# LPCB221_-_G210X_INTERFACE.net
KiCad netlist of a schematic drawn in Altium Designer
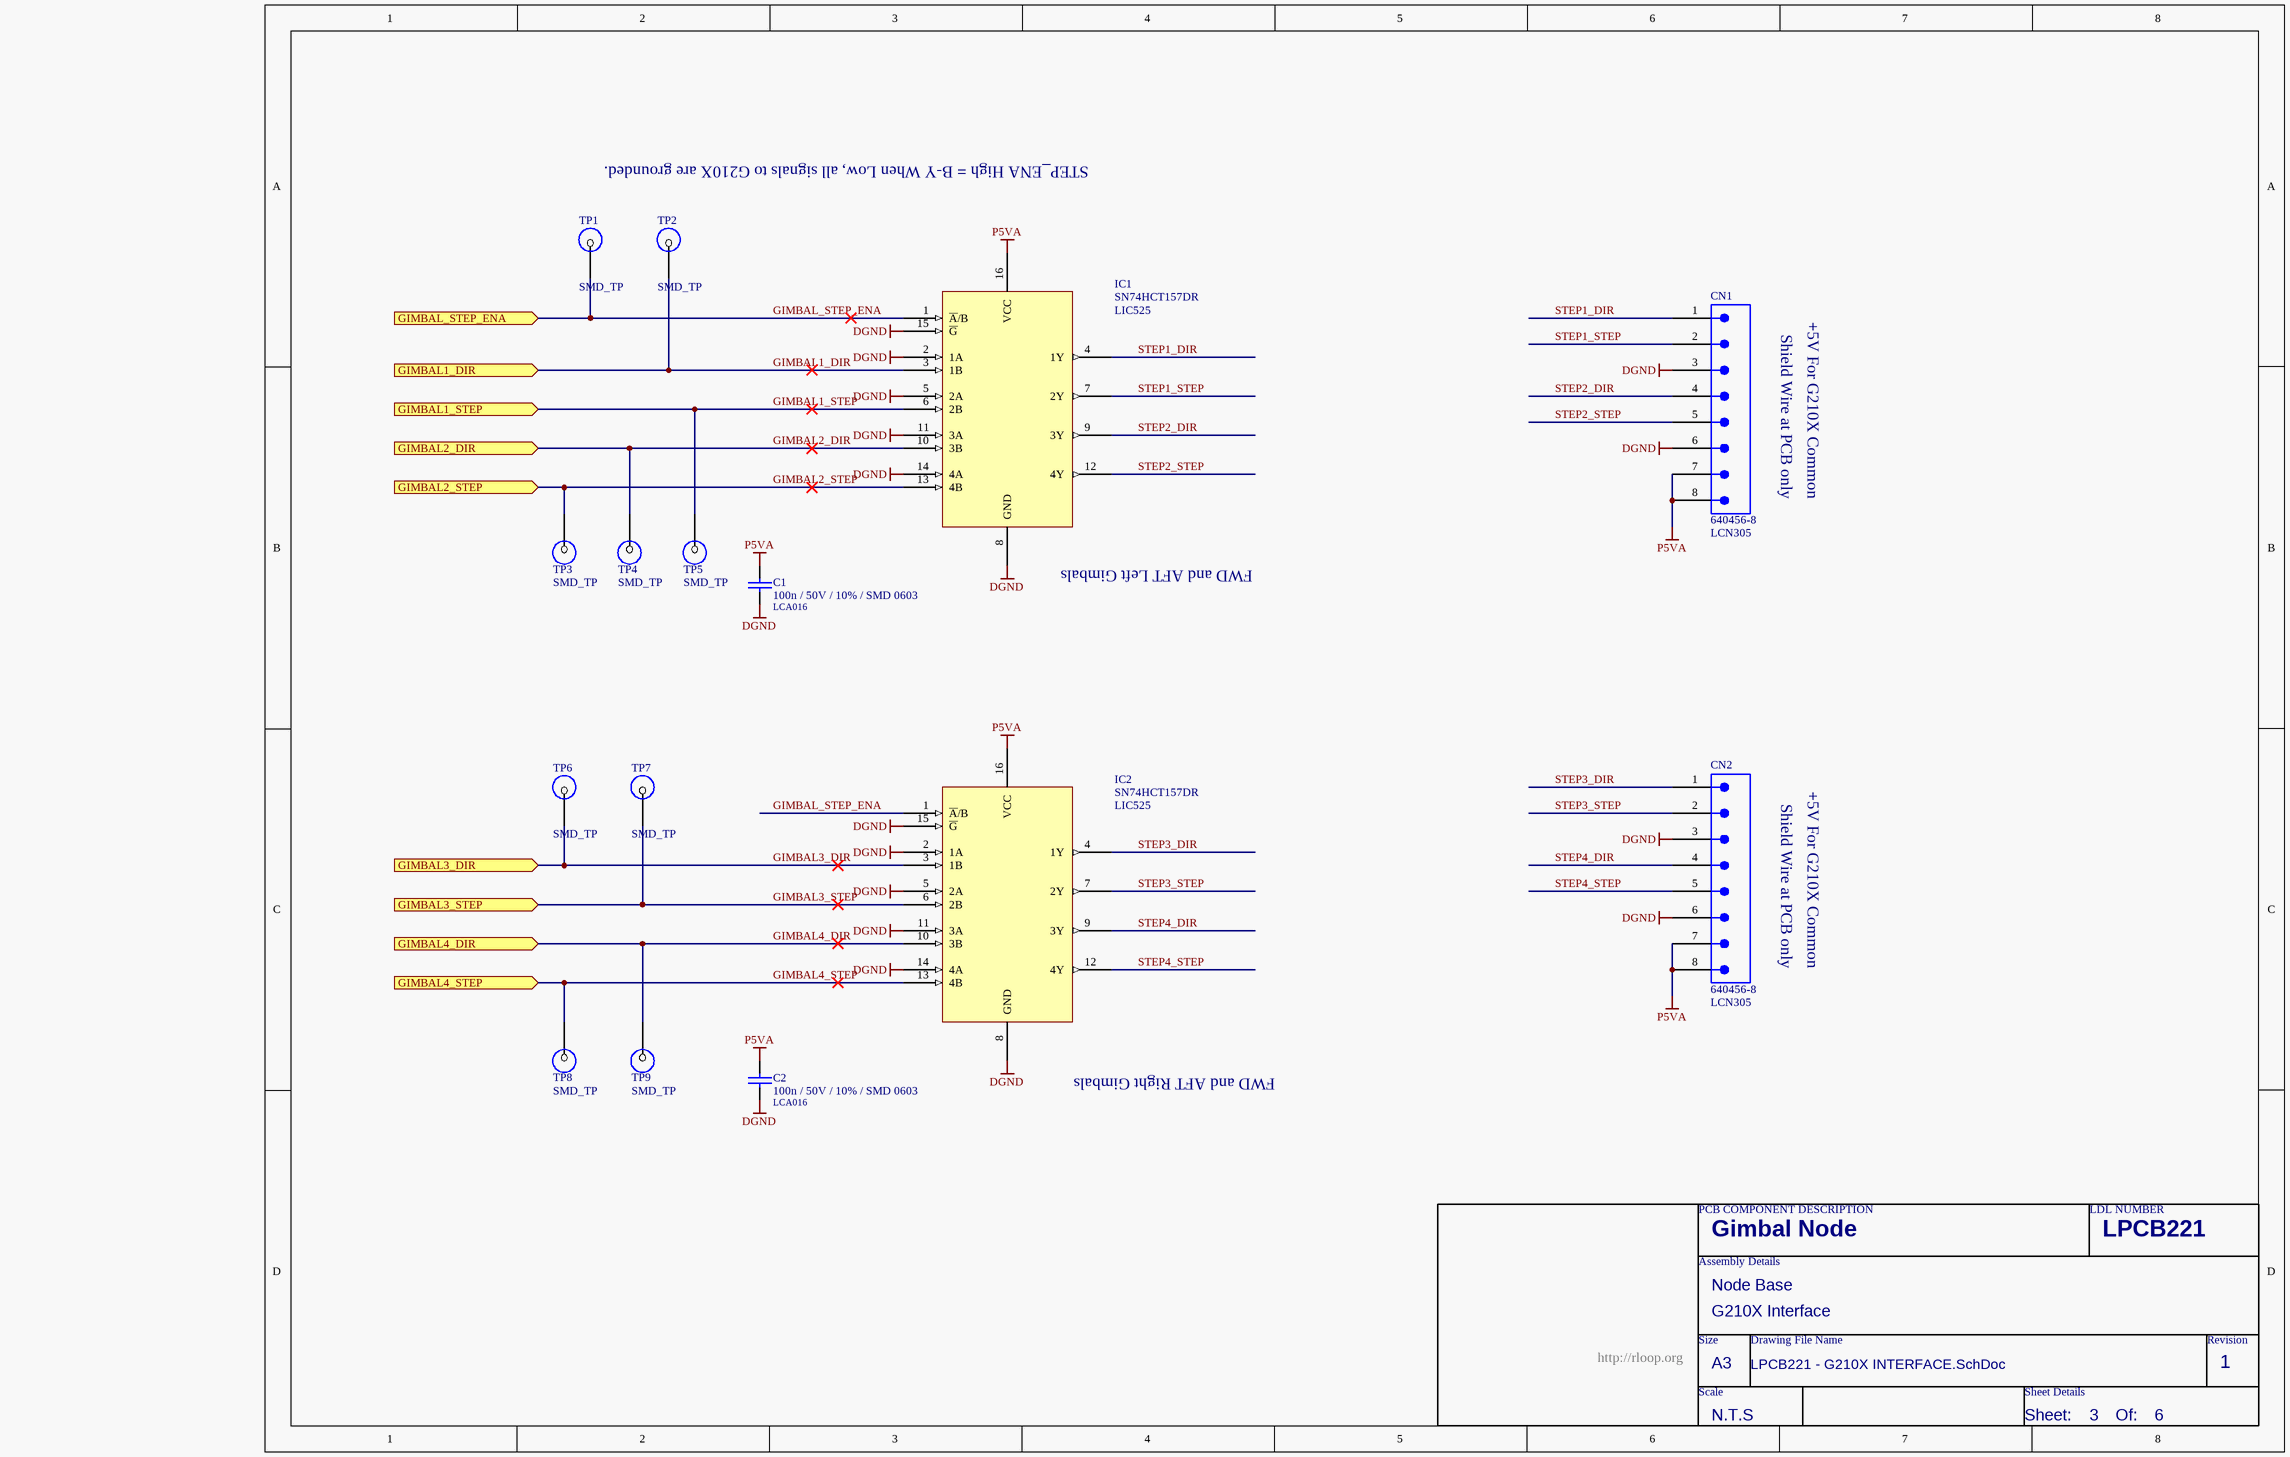
[diagram p0: LPCB221 - G210X INTERFACE.SchDoc]

(export (version "E")
  (design (tool "Eeschema 10.0.6"))
  (components
    (comp (ref "C1")
      (value "100n / 50V / 10% / SMD 0603")
      (footprint "LFP011__CC1608-0603-IPC7351_B")
      (description "Capacitor, Ceramic Chip, 100nF (0.1uF), 50V, 5%, SMD 0603 [LCA016]")
      (fields (field (name "LDL_NUMBER") "LCA016"))
      (libsource (lib "LDL_Capacitors") (part "100n / 50V / 10% / SMD 0603"))
    )
    (comp (ref "C2")
      (value "100n / 50V / 10% / SMD 0603")
      (footprint "LFP011__CC1608-0603-IPC7351_B")
      (description "Capacitor, Ceramic Chip, 100nF (0.1uF), 50V, 5%, SMD 0603 [LCA016]")
      (fields (field (name "LDL_NUMBER") "LCA016"))
      (libsource (lib "LDL_Capacitors") (part "100n / 50V / 10% / SMD 0603"))
    )
    (comp (ref "CN1")
      (value "640456-8")
      (footprint "640456-8")
      (description "Connector, Male Header, 8 Way")
      (fields (field (name "LDL_NUMBER") "LCN305"))
      (libsource (lib "LDL_Connectors") (part "640456-8"))
    )
    (comp (ref "CN2")
      (value "640456-8")
      (footprint "640456-8")
      (description "Connector, Male Header, 8 Way")
      (fields (field (name "LDL_NUMBER") "LCN305"))
      (libsource (lib "LDL_Connectors") (part "640456-8"))
    )
    (comp (ref "IC1")
      (value "SN74HCT157DR")
      (footprint "LFP079__SOP16")
      (description "IC, Multiplexer Select 2-1 [LIC525]")
      (fields (field (name "LDL_NUMBER") "LIC525"))
      (libsource (lib "LDL_Semiconductors") (part "SN74HCT157DR"))
    )
    (comp (ref "IC2")
      (value "SN74HCT157DR")
      (footprint "LFP079__SOP16")
      (description "IC, Multiplexer Select 2-1 [LIC525]")
      (fields (field (name "LDL_NUMBER") "LIC525"))
      (libsource (lib "LDL_Semiconductors") (part "SN74HCT157DR"))
    )
    (comp (ref "TP1")
      (value "SMD_TP")
      (footprint "SMD-TP")
      (description "SMD Test Point")
      (libsource (lib "LDL_Connectors") (part "SMD_TP"))
    )
    (comp (ref "TP2")
      (value "SMD_TP")
      (footprint "SMD-TP")
      (description "SMD Test Point")
      (libsource (lib "LDL_Connectors") (part "SMD_TP"))
    )
    (comp (ref "TP3")
      (value "SMD_TP")
      (footprint "SMD-TP")
      (description "SMD Test Point")
      (libsource (lib "LDL_Connectors") (part "SMD_TP"))
    )
    (comp (ref "TP4")
      (value "SMD_TP")
      (footprint "SMD-TP")
      (description "SMD Test Point")
      (libsource (lib "LDL_Connectors") (part "SMD_TP"))
    )
    (comp (ref "TP5")
      (value "SMD_TP")
      (footprint "SMD-TP")
      (description "SMD Test Point")
      (libsource (lib "LDL_Connectors") (part "SMD_TP"))
    )
    (comp (ref "TP6")
      (value "SMD_TP")
      (footprint "SMD-TP")
      (description "SMD Test Point")
      (libsource (lib "LDL_Connectors") (part "SMD_TP"))
    )
    (comp (ref "TP7")
      (value "SMD_TP")
      (footprint "SMD-TP")
      (description "SMD Test Point")
      (libsource (lib "LDL_Connectors") (part "SMD_TP"))
    )
    (comp (ref "TP8")
      (value "SMD_TP")
      (footprint "SMD-TP")
      (description "SMD Test Point")
      (libsource (lib "LDL_Connectors") (part "SMD_TP"))
    )
    (comp (ref "TP9")
      (value "SMD_TP")
      (footprint "SMD-TP")
      (description "SMD Test Point")
      (libsource (lib "LDL_Connectors") (part "SMD_TP"))
    )
  )
  (nets
    (net (code "1") (name "/GIMBAL1_DIR") (class "Default")
      (node (ref "IC1") (pin "3") (pinfunction "1B_3") (pintype "input"))
      (node (ref "TP2") (pin "1") (pintype "passive"))
    )
    (net (code "2") (name "/GIMBAL1_STEP") (class "Default")
      (node (ref "IC1") (pin "6") (pinfunction "2B_6") (pintype "input"))
      (node (ref "TP5") (pin "1") (pintype "passive"))
    )
    (net (code "3") (name "/GIMBAL2_DIR") (class "Default")
      (node (ref "IC1") (pin "10") (pinfunction "3B_10") (pintype "input"))
      (node (ref "TP4") (pin "1") (pintype "passive"))
    )
    (net (code "4") (name "/GIMBAL2_STEP") (class "Default")
      (node (ref "IC1") (pin "13") (pinfunction "4B_13") (pintype "input"))
      (node (ref "TP3") (pin "1") (pintype "passive"))
    )
    (net (code "5") (name "/GIMBAL3_DIR") (class "Default")
      (node (ref "IC2") (pin "3") (pinfunction "1B_3") (pintype "input"))
      (node (ref "TP6") (pin "1") (pintype "passive"))
    )
    (net (code "6") (name "/GIMBAL3_STEP") (class "Default")
      (node (ref "IC2") (pin "6") (pinfunction "2B_6") (pintype "input"))
      (node (ref "TP7") (pin "1") (pintype "passive"))
    )
    (net (code "7") (name "/GIMBAL4_DIR") (class "Default")
      (node (ref "IC2") (pin "10") (pinfunction "3B_10") (pintype "input"))
      (node (ref "TP9") (pin "1") (pintype "passive"))
    )
    (net (code "8") (name "/GIMBAL4_STEP") (class "Default")
      (node (ref "IC2") (pin "13") (pinfunction "4B_13") (pintype "input"))
      (node (ref "TP8") (pin "1") (pintype "passive"))
    )
    (net (code "9") (name "/GIMBAL_STEP_ENA") (class "Default")
      (node (ref "IC1") (pin "1") (pinfunction "~{A}/B_1") (pintype "input"))
      (node (ref "IC2") (pin "1") (pinfunction "~{A}/B_1") (pintype "input"))
      (node (ref "TP1") (pin "1") (pintype "passive"))
    )
    (net (code "10") (name "/STEP1_DIR") (class "Default")
      (node (ref "CN1") (pin "1") (pinfunction "1_1") (pintype "passive"))
      (node (ref "IC1") (pin "4") (pinfunction "1Y_4") (pintype "output"))
    )
    (net (code "11") (name "/STEP1_STEP") (class "Default")
      (node (ref "CN1") (pin "2") (pinfunction "2_2") (pintype "passive"))
      (node (ref "IC1") (pin "7") (pinfunction "2Y_7") (pintype "output"))
    )
    (net (code "12") (name "/STEP2_DIR") (class "Default")
      (node (ref "CN1") (pin "4") (pinfunction "4_4") (pintype "passive"))
      (node (ref "IC1") (pin "9") (pinfunction "3Y_9") (pintype "output"))
    )
    (net (code "13") (name "/STEP2_STEP") (class "Default")
      (node (ref "CN1") (pin "5") (pinfunction "5_5") (pintype "passive"))
      (node (ref "IC1") (pin "12") (pinfunction "4Y_12") (pintype "output"))
    )
    (net (code "14") (name "/STEP3_DIR") (class "Default")
      (node (ref "CN2") (pin "1") (pinfunction "1_1") (pintype "passive"))
      (node (ref "IC2") (pin "4") (pinfunction "1Y_4") (pintype "output"))
    )
    (net (code "15") (name "/STEP3_STEP") (class "Default")
      (node (ref "CN2") (pin "2") (pinfunction "2_2") (pintype "passive"))
      (node (ref "IC2") (pin "7") (pinfunction "2Y_7") (pintype "output"))
    )
    (net (code "16") (name "/STEP4_DIR") (class "Default")
      (node (ref "CN2") (pin "4") (pinfunction "4_4") (pintype "passive"))
      (node (ref "IC2") (pin "9") (pinfunction "3Y_9") (pintype "output"))
    )
    (net (code "17") (name "/STEP4_STEP") (class "Default")
      (node (ref "CN2") (pin "5") (pinfunction "5_5") (pintype "passive"))
      (node (ref "IC2") (pin "12") (pinfunction "4Y_12") (pintype "output"))
    )
    (net (code "18") (name "DGND") (class "Default")
      (node (ref "C1") (pin "2") (pintype "passive"))
      (node (ref "C2") (pin "2") (pintype "passive"))
      (node (ref "CN1") (pin "3") (pinfunction "3_3") (pintype "passive"))
      (node (ref "CN1") (pin "6") (pinfunction "6_6") (pintype "passive"))
      (node (ref "CN2") (pin "3") (pinfunction "3_3") (pintype "passive"))
      (node (ref "CN2") (pin "6") (pinfunction "6_6") (pintype "passive"))
      (node (ref "IC1") (pin "11") (pinfunction "3A_11") (pintype "input"))
      (node (ref "IC1") (pin "14") (pinfunction "4A_14") (pintype "input"))
      (node (ref "IC1") (pin "15") (pinfunction "~{G}_15") (pintype "input"))
      (node (ref "IC1") (pin "2") (pinfunction "1A_2") (pintype "input"))
      (node (ref "IC1") (pin "5") (pinfunction "2A_5") (pintype "input"))
      (node (ref "IC1") (pin "8") (pinfunction "GND_8") (pintype "power_in"))
      (node (ref "IC2") (pin "11") (pinfunction "3A_11") (pintype "input"))
      (node (ref "IC2") (pin "14") (pinfunction "4A_14") (pintype "input"))
      (node (ref "IC2") (pin "15") (pinfunction "~{G}_15") (pintype "input"))
      (node (ref "IC2") (pin "2") (pinfunction "1A_2") (pintype "input"))
      (node (ref "IC2") (pin "5") (pinfunction "2A_5") (pintype "input"))
      (node (ref "IC2") (pin "8") (pinfunction "GND_8") (pintype "power_in"))
    )
    (net (code "19") (name "P5VA") (class "Default")
      (node (ref "C1") (pin "1") (pintype "passive"))
      (node (ref "C2") (pin "1") (pintype "passive"))
      (node (ref "CN1") (pin "7") (pinfunction "7_7") (pintype "passive"))
      (node (ref "CN1") (pin "8") (pinfunction "8_8") (pintype "passive"))
      (node (ref "CN2") (pin "7") (pinfunction "7_7") (pintype "passive"))
      (node (ref "CN2") (pin "8") (pinfunction "8_8") (pintype "passive"))
      (node (ref "IC1") (pin "16") (pinfunction "VCC_16") (pintype "power_in"))
      (node (ref "IC2") (pin "16") (pinfunction "VCC_16") (pintype "power_in"))
    )
  )
)
